# placaTemporizadora.net
KiCad netlist of a schematic drawn in Altium Designer
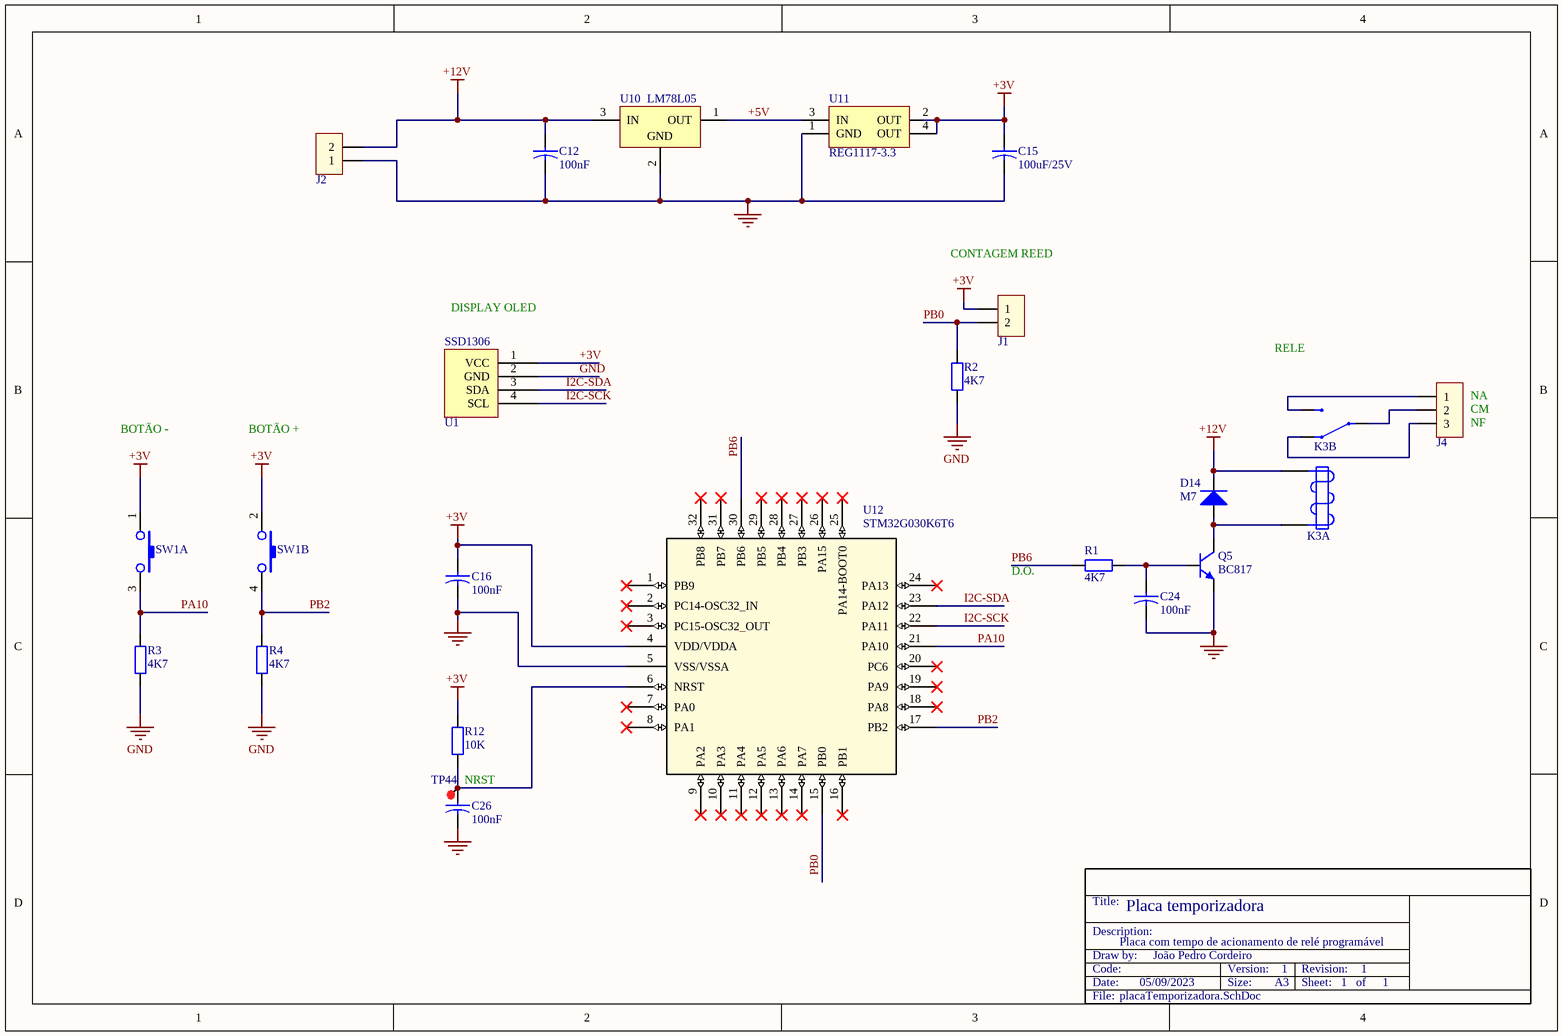
[diagram p0: placaTemporizadora.SchDoc]

(export (version "E")
  (design (tool "Eeschema 10.0.6"))
  (components
    (comp (ref "C12")
      (value "100nF")
      (footprint "0805-CAP")
      (description "CAPACITOR CERAMICO 100NF (100KPF) -60V 0805 NP0 SMD")
      (libsource (lib "LIB_ROSSI") (part "CAP100N_0805"))
    )
    (comp (ref "C15")
      (value "100uF/25V")
      (footprint "CAP-POL-P3.0")
      (description "CAPACITOR ELETROL. RADIAL 100UF-25V P-2.5MM X A-4MM FT")
      (libsource (lib "LIB_ROSSI") (part "CAP100U_POL"))
    )
    (comp (ref "C16")
      (value "100nF")
      (footprint "0805-CAP")
      (description "CAPACITOR CERAMICO 100NF (100KPF) -60V 0805 NP0 SMD")
      (libsource (lib "LIB_ROSSI") (part "CAP100N_0805"))
    )
    (comp (ref "C24")
      (value "100nF")
      (footprint "0805-CAP")
      (description "CAPACITOR CERAMICO 100NF (100KPF) -60V 0805 NP0 SMD")
      (libsource (lib "LIB_ROSSI") (part "CAP100N_0805"))
    )
    (comp (ref "C26")
      (value "100nF")
      (footprint "0805-CAP")
      (description "CAPACITOR CERAMICO 100NF (100KPF) -60V 0805 NP0 SMD")
      (libsource (lib "LIB_ROSSI") (part "CAP100N_0805"))
    )
    (comp (ref "D14")
      (value "M7")
      (footprint "SMA")
      (description "DIODO M7 SMD")
      (libsource (lib "LIB_ROSSI") (part "M7"))
    )
    (comp (ref "J1")
      (value "BORNE")
      (footprint "BORNE2")
      (description "BORNE CI 02P COM MOLA VERDE - 112.064.13")
      (libsource (lib "LIB_ROSSI") (part "BORNE2"))
    )
    (comp (ref "J2")
      (value "BORNE")
      (footprint "BORNE2")
      (description "BORNE CI 02P COM MOLA VERDE - 112.064.13")
      (libsource (lib "") (part "BORNE2_1"))
    )
    (comp (ref "J4")
      (value "BORNE")
      (footprint "BORNE3")
      (description "BORNE CI 03P COM MOLA VERDE - 112.063.12")
      (libsource (lib "LIB_ROSSI") (part "BORNE3"))
    )
    (comp (ref "K3")
      (value "RELE10A")
      (footprint "RELE12V_NCR")
      (description "RELE ROSSI CF413012-15A OU A1022")
      (libsource (lib "LIB_ROSSI") (part "RELE10A"))
    )
    (comp (ref "Q5")
      (value "BC817")
      (footprint "SOT-23")
      (description "TRANSISTOR BC817-25 SOT-23 SMD")
      (libsource (lib "LIB_ROSSI") (part "BC817"))
    )
    (comp (ref "R1")
      (value "4K7")
      (footprint "0805-RES")
      (description "RESISTOR 4K7 0805 5% SMD")
      (libsource (lib "LIB_ROSSI") (part "RES4K7_0805"))
    )
    (comp (ref "R2")
      (value "4K7")
      (footprint "0805-RES")
      (description "RESISTOR 4K7 0805 5% SMD")
      (libsource (lib "LIB_ROSSI") (part "RES4K7_0805"))
    )
    (comp (ref "R3")
      (value "4K7")
      (footprint "0805-RES")
      (description "RESISTOR 4K7 0805 5% SMD")
      (libsource (lib "LIB_ROSSI") (part "RES4K7_0805"))
    )
    (comp (ref "R4")
      (value "4K7")
      (footprint "0805-RES")
      (description "RESISTOR 4K7 0805 5% SMD")
      (libsource (lib "LIB_ROSSI") (part "RES4K7_0805"))
    )
    (comp (ref "R12")
      (value "10K")
      (footprint "0805-RES")
      (description "RESISTOR 10K 0805 1% SMD")
      (libsource (lib "LIB_ROSSI") (part "RES10K_0805_1"))
    )
    (comp (ref "SW1")
      (value "LT4TH243-T")
      (footprint "PUSHBUTTON_PTH")
      (description "MICRO-CHAVE TACTIL 4.3MM BASE METALICA COM SILICA-GEL LT4TH243-T  L=3.1")
      (libsource (lib "LIB_ROSSI") (part "PUSHBUTTON_PTH"))
    )
    (comp (ref "TP44")
      (value "testepoint")
      (footprint "TESTPOINT")
      (libsource (lib "LIB_ROSSI") (part "TESTEPOINT"))
    )
    (comp (ref "U1")
      (value "SSD1306")
      (description "DISPLAY OLED I2C")
      (libsource (lib "OLED") (part "SSD1306"))
    )
    (comp (ref "U10")
      (value "LM78L05")
      (footprint "TO-92")
      (description "CI. REGULADOR DE TENSAO 78L05 FT (TO92)")
      (libsource (lib "LIB_ROSSI") (part "LM78L05"))
    )
    (comp (ref "U11")
      (value "REG1117-3.3")
      (footprint "SOT-223B")
      (description "REGULADOR LDO 3.3V 800MA SOT-223 SMD")
      (libsource (lib "LIB_ROSSI") (part "REG1117-3.3"))
    )
    (comp (ref "U12")
      (value "STM32G030K6T6")
      (footprint "LQFP-32")
      (description "CI STM32G030K6T6 ST SMD MCU ARM M0")
      (libsource (lib "LIB_ROSSI") (part "STM32G030K6"))
    )
  )
  (nets
    (net (code "1") (name "+3V") (class "Default")
      (node (ref "C15") (pin "2") (pinfunction "2_2") (pintype "passive"))
      (node (ref "C16") (pin "2") (pinfunction "2_2") (pintype "passive"))
      (node (ref "J1") (pin "1") (pinfunction "1_1") (pintype "passive"))
      (node (ref "R12") (pin "2") (pinfunction "2_2") (pintype "passive"))
      (node (ref "SW1") (pin "1") (pinfunction "1_1") (pintype "passive"))
      (node (ref "SW1") (pin "2") (pinfunction "2_2") (pintype "passive"))
      (node (ref "U1") (pin "1") (pinfunction "VCC_1") (pintype "passive"))
      (node (ref "U11") (pin "2") (pinfunction "OUT_2") (pintype "power_in"))
      (node (ref "U11") (pin "4") (pinfunction "OUT_4") (pintype "power_in"))
      (node (ref "U12") (pin "4") (pinfunction "VDD/VDDA_4") (pintype "power_in"))
    )
    (net (code "2") (name "+12V") (class "Default")
      (node (ref "C12") (pin "2") (pinfunction "2_2") (pintype "passive"))
      (node (ref "D14") (pin "1") (pinfunction "1_1") (pintype "passive"))
      (node (ref "J2") (pin "2") (pinfunction "2_2") (pintype "passive"))
      (node (ref "K3") (pin "4") (pinfunction "4_4") (pintype "passive"))
      (node (ref "U10") (pin "3") (pinfunction "IN_3") (pintype "power_in"))
    )
    (net (code "3") (name "/+5V") (class "Default")
      (node (ref "U10") (pin "1") (pinfunction "OUT_1") (pintype "power_in"))
      (node (ref "U11") (pin "3") (pinfunction "IN_3") (pintype "power_in"))
    )
    (net (code "4") (name "/I2C-SCK") (class "Default")
      (node (ref "U1") (pin "4") (pinfunction "SCL_4") (pintype "passive"))
      (node (ref "U12") (pin "22") (pinfunction "PA11_22") (pintype "bidirectional"))
    )
    (net (code "5") (name "/I2C-SDA") (class "Default")
      (node (ref "U1") (pin "3") (pinfunction "SDA_3") (pintype "passive"))
      (node (ref "U12") (pin "23") (pinfunction "PA12_23") (pintype "bidirectional"))
    )
    (net (code "6") (name "/PA10") (class "Default")
      (node (ref "R3") (pin "2") (pinfunction "2_2") (pintype "passive"))
      (node (ref "SW1") (pin "3") (pinfunction "3_3") (pintype "passive"))
      (node (ref "U12") (pin "21") (pinfunction "PA10_21") (pintype "bidirectional"))
    )
    (net (code "7") (name "/PB0") (class "Default")
      (node (ref "J1") (pin "2") (pinfunction "2_2") (pintype "passive"))
      (node (ref "R2") (pin "2") (pinfunction "2_2") (pintype "passive"))
      (node (ref "U12") (pin "15") (pinfunction "PB0_15") (pintype "bidirectional"))
    )
    (net (code "8") (name "/PB2") (class "Default")
      (node (ref "R4") (pin "2") (pinfunction "2_2") (pintype "passive"))
      (node (ref "SW1") (pin "4") (pinfunction "4_4") (pintype "passive"))
      (node (ref "U12") (pin "17") (pinfunction "PB2_17") (pintype "bidirectional"))
    )
    (net (code "9") (name "/PB6") (class "Default")
      (node (ref "R1") (pin "1") (pinfunction "1_1") (pintype "passive"))
      (node (ref "U12") (pin "30") (pinfunction "PB6_30") (pintype "bidirectional"))
    )
    (net (code "10") (name "GND") (class "Default")
      (node (ref "C12") (pin "1") (pinfunction "1_1") (pintype "passive"))
      (node (ref "C15") (pin "1") (pinfunction "1_1") (pintype "passive"))
      (node (ref "C16") (pin "1") (pinfunction "1_1") (pintype "passive"))
      (node (ref "C24") (pin "1") (pinfunction "1_1") (pintype "passive"))
      (node (ref "C26") (pin "1") (pinfunction "1_1") (pintype "passive"))
      (node (ref "J2") (pin "1") (pinfunction "1_1") (pintype "passive"))
      (node (ref "Q5") (pin "2") (pinfunction "E_2") (pintype "passive"))
      (node (ref "R2") (pin "1") (pinfunction "1_1") (pintype "passive"))
      (node (ref "R3") (pin "1") (pinfunction "1_1") (pintype "passive"))
      (node (ref "R4") (pin "1") (pinfunction "1_1") (pintype "passive"))
      (node (ref "U1") (pin "2") (pinfunction "GND_2") (pintype "passive"))
      (node (ref "U10") (pin "2") (pinfunction "GND_2") (pintype "power_in"))
      (node (ref "U11") (pin "1") (pinfunction "GND_1") (pintype "power_in"))
      (node (ref "U12") (pin "5") (pinfunction "VSS/VSSA_5") (pintype "power_in"))
    )
    (net (code "11") (name "Net-(J4-Pad1)") (class "Default")
      (node (ref "J4") (pin "1") (pinfunction "1_1") (pintype "passive"))
      (node (ref "K3") (pin "3") (pinfunction "3_3") (pintype "passive"))
    )
    (net (code "12") (name "Net-(J4-Pad2)") (class "Default")
      (node (ref "J4") (pin "2") (pinfunction "2_2") (pintype "passive"))
      (node (ref "K3") (pin "1") (pinfunction "1_1") (pintype "passive"))
    )
    (net (code "13") (name "Net-(J4-Pad3)") (class "Default")
      (node (ref "J4") (pin "3") (pinfunction "3_3") (pintype "passive"))
      (node (ref "K3") (pin "2") (pinfunction "2_2") (pintype "passive"))
    )
    (net (code "14") (name "Net-(Q5-10)") (class "Default")
      (node (ref "C24") (pin "2") (pinfunction "2_2") (pintype "passive"))
      (node (ref "Q5") (pin "1") (pinfunction "10_1") (pintype "passive"))
      (node (ref "R1") (pin "2") (pinfunction "2_2") (pintype "passive"))
    )
    (net (code "15") (name "Net-(Q5-C)") (class "Default")
      (node (ref "D14") (pin "2") (pinfunction "2_2") (pintype "passive"))
      (node (ref "K3") (pin "5") (pinfunction "5_5") (pintype "passive"))
      (node (ref "Q5") (pin "3") (pinfunction "C_3") (pintype "passive"))
    )
    (net (code "16") (name "Net-(U12-NRST)") (class "Default")
      (node (ref "C26") (pin "2") (pinfunction "2_2") (pintype "passive"))
      (node (ref "R12") (pin "1") (pinfunction "1_1") (pintype "passive"))
      (node (ref "TP44") (pin "1") (pinfunction "1_1") (pintype "passive"))
      (node (ref "U12") (pin "6") (pinfunction "NRST_6") (pintype "bidirectional"))
    )
    (net (code "17") (name "unconnected-(U12-PA0-Pad7)") (class "Default")
      (node (ref "U12") (pin "7") (pinfunction "PA0_7") (pintype "bidirectional+no_connect"))
    )
    (net (code "18") (name "unconnected-(U12-PA1-Pad8)") (class "Default")
      (node (ref "U12") (pin "8") (pinfunction "PA1_8") (pintype "bidirectional+no_connect"))
    )
    (net (code "19") (name "unconnected-(U12-PA2-Pad9)") (class "Default")
      (node (ref "U12") (pin "9") (pinfunction "PA2_9") (pintype "bidirectional+no_connect"))
    )
    (net (code "20") (name "unconnected-(U12-PA3-Pad10)") (class "Default")
      (node (ref "U12") (pin "10") (pinfunction "PA3_10") (pintype "bidirectional+no_connect"))
    )
    (net (code "21") (name "unconnected-(U12-PA4-Pad11)") (class "Default")
      (node (ref "U12") (pin "11") (pinfunction "PA4_11") (pintype "bidirectional+no_connect"))
    )
    (net (code "22") (name "unconnected-(U12-PA5-Pad12)") (class "Default")
      (node (ref "U12") (pin "12") (pinfunction "PA5_12") (pintype "bidirectional+no_connect"))
    )
    (net (code "23") (name "unconnected-(U12-PA6-Pad13)") (class "Default")
      (node (ref "U12") (pin "13") (pinfunction "PA6_13") (pintype "bidirectional+no_connect"))
    )
    (net (code "24") (name "unconnected-(U12-PA7-Pad14)") (class "Default")
      (node (ref "U12") (pin "14") (pinfunction "PA7_14") (pintype "bidirectional+no_connect"))
    )
    (net (code "25") (name "unconnected-(U12-PA8-Pad18)") (class "Default")
      (node (ref "U12") (pin "18") (pinfunction "PA8_18") (pintype "bidirectional+no_connect"))
    )
    (net (code "26") (name "unconnected-(U12-PA9-Pad19)") (class "Default")
      (node (ref "U12") (pin "19") (pinfunction "PA9_19") (pintype "bidirectional+no_connect"))
    )
    (net (code "27") (name "unconnected-(U12-PA13-Pad24)") (class "Default")
      (node (ref "U12") (pin "24") (pinfunction "PA13_24") (pintype "bidirectional+no_connect"))
    )
    (net (code "28") (name "unconnected-(U12-PA14-BOOT0-Pad25)") (class "Default")
      (node (ref "U12") (pin "25") (pinfunction "PA14-BOOT0_25") (pintype "bidirectional+no_connect"))
    )
    (net (code "29") (name "unconnected-(U12-PA15-Pad26)") (class "Default")
      (node (ref "U12") (pin "26") (pinfunction "PA15_26") (pintype "bidirectional+no_connect"))
    )
    (net (code "30") (name "unconnected-(U12-PB1-Pad16)") (class "Default")
      (node (ref "U12") (pin "16") (pinfunction "PB1_16") (pintype "bidirectional+no_connect"))
    )
    (net (code "31") (name "unconnected-(U12-PB3-Pad27)") (class "Default")
      (node (ref "U12") (pin "27") (pinfunction "PB3_27") (pintype "bidirectional+no_connect"))
    )
    (net (code "32") (name "unconnected-(U12-PB4-Pad28)") (class "Default")
      (node (ref "U12") (pin "28") (pinfunction "PB4_28") (pintype "bidirectional+no_connect"))
    )
    (net (code "33") (name "unconnected-(U12-PB5-Pad29)") (class "Default")
      (node (ref "U12") (pin "29") (pinfunction "PB5_29") (pintype "bidirectional+no_connect"))
    )
    (net (code "34") (name "unconnected-(U12-PB7-Pad31)") (class "Default")
      (node (ref "U12") (pin "31") (pinfunction "PB7_31") (pintype "bidirectional+no_connect"))
    )
    (net (code "35") (name "unconnected-(U12-PB8-Pad32)") (class "Default")
      (node (ref "U12") (pin "32") (pinfunction "PB8_32") (pintype "bidirectional+no_connect"))
    )
    (net (code "36") (name "unconnected-(U12-PB9-Pad1)") (class "Default")
      (node (ref "U12") (pin "1") (pinfunction "PB9_1") (pintype "bidirectional+no_connect"))
    )
    (net (code "37") (name "unconnected-(U12-PC6-Pad20)") (class "Default")
      (node (ref "U12") (pin "20") (pinfunction "PC6_20") (pintype "bidirectional+no_connect"))
    )
    (net (code "38") (name "unconnected-(U12-PC14-OSC32_IN-Pad2)") (class "Default")
      (node (ref "U12") (pin "2") (pinfunction "PC14-OSC32_IN_2") (pintype "bidirectional+no_connect"))
    )
    (net (code "39") (name "unconnected-(U12-PC15-OSC32_OUT-Pad3)") (class "Default")
      (node (ref "U12") (pin "3") (pinfunction "PC15-OSC32_OUT_3") (pintype "bidirectional+no_connect"))
    )
  )
)
